# Clock_Led_7_thanh_Huynh_Tan_Cuong.net
KiCad netlist of a schematic drawn in Altium Designer
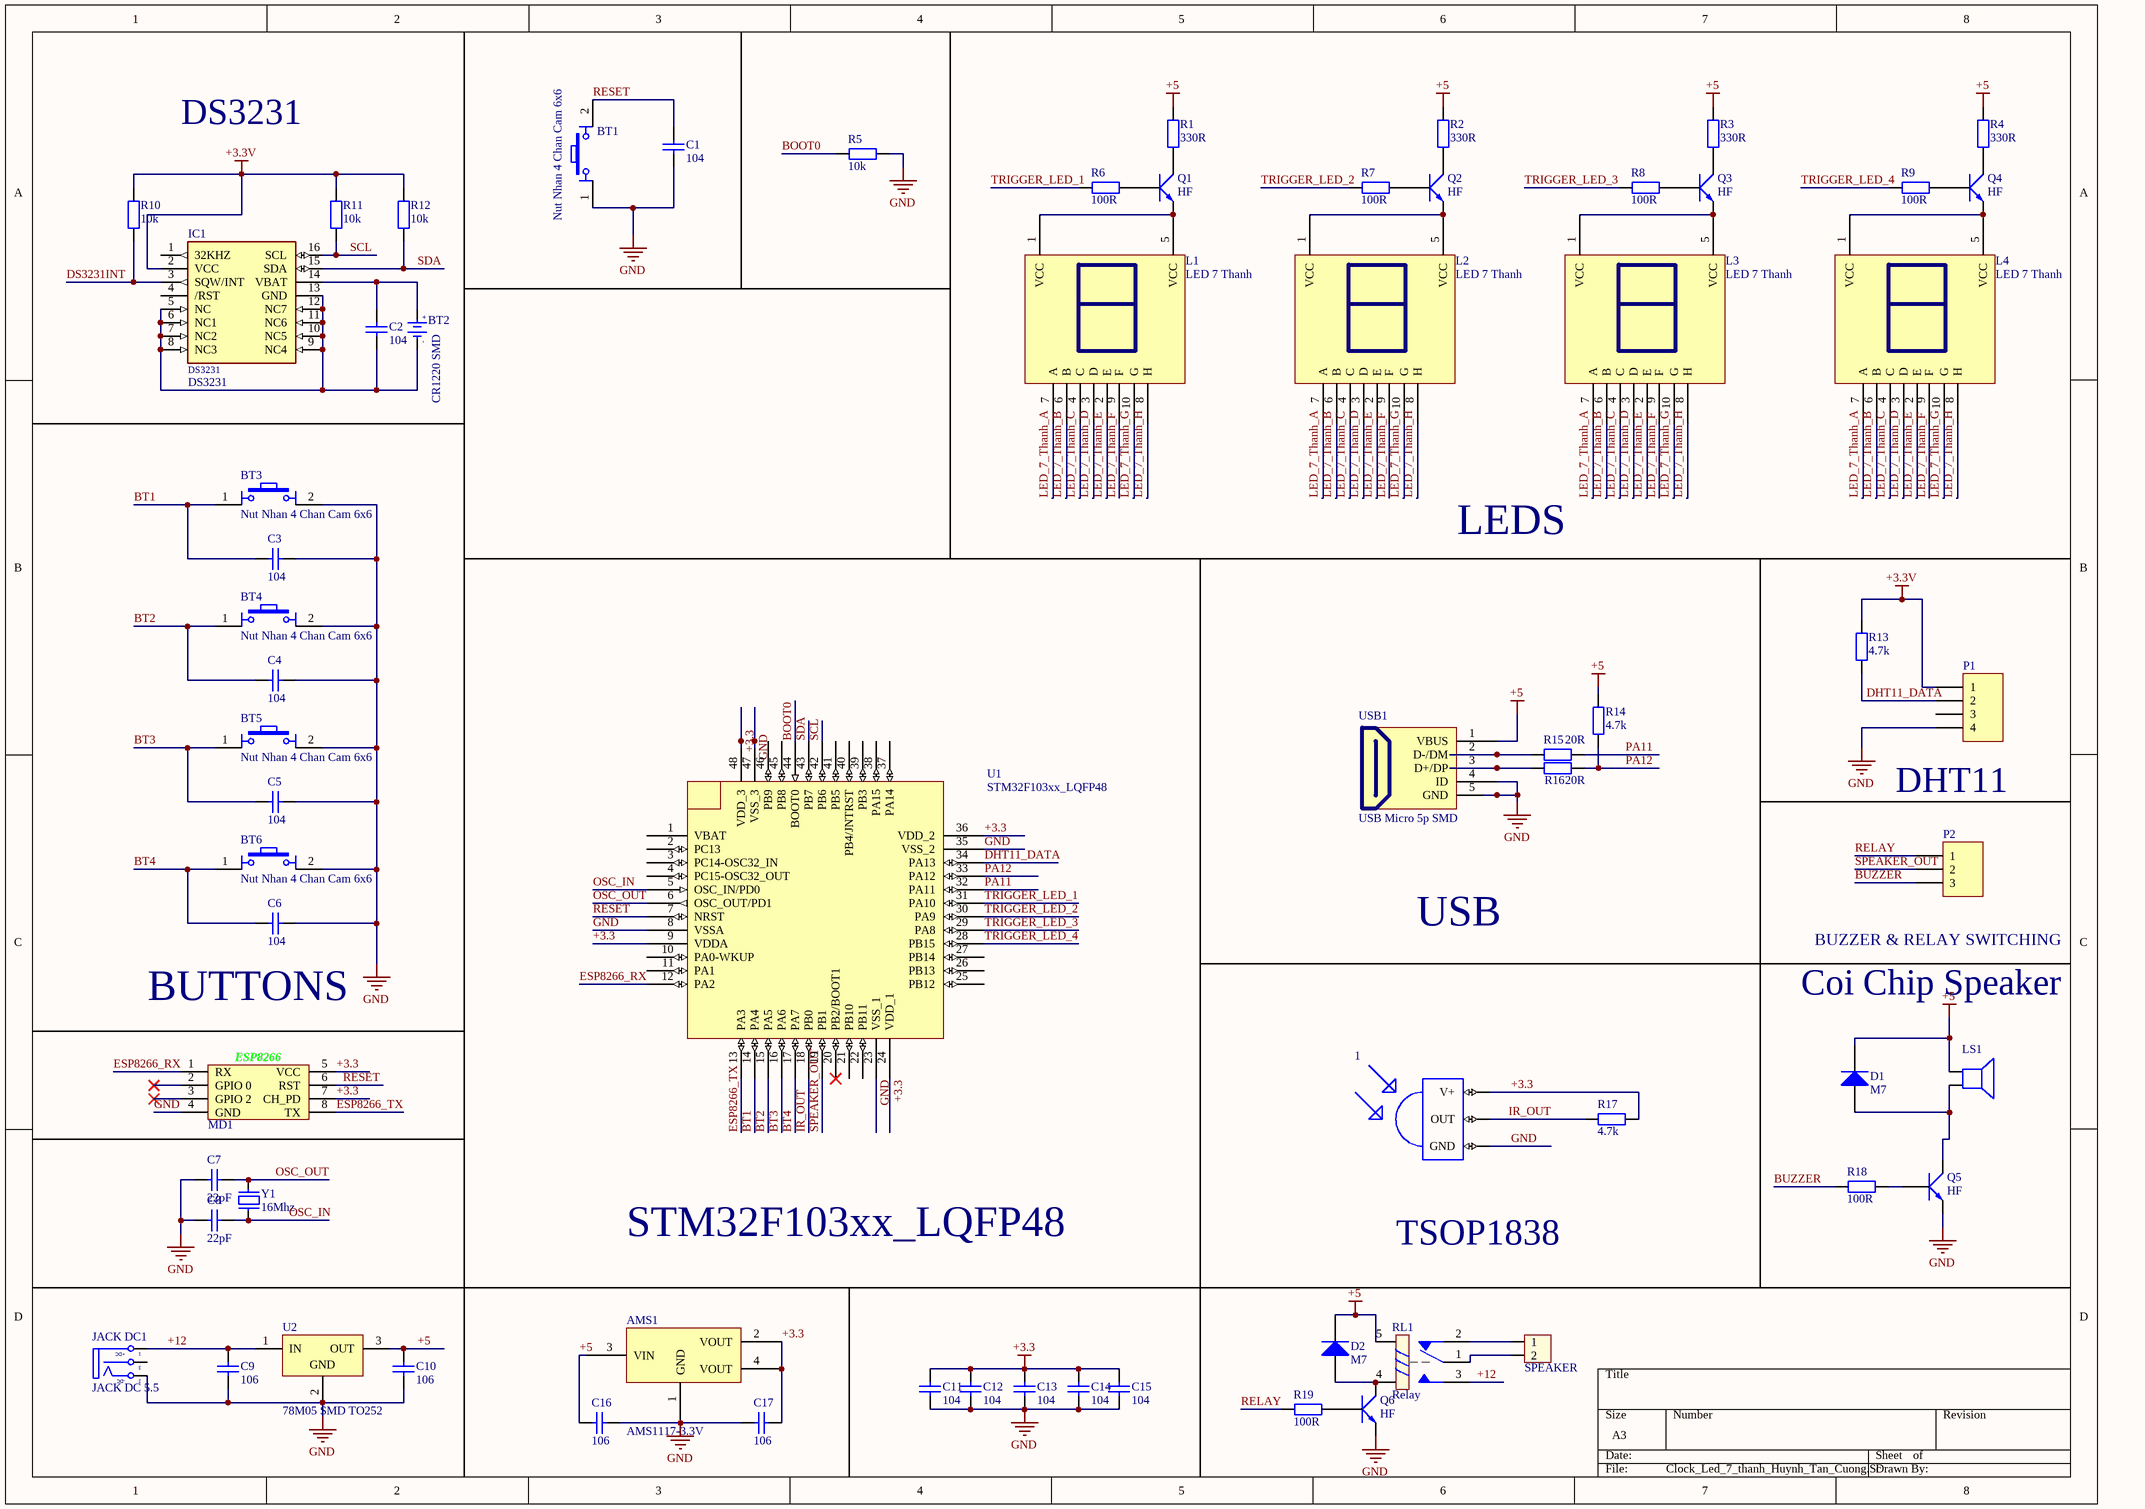
[diagram p0: Clock_Led_7_thanh_Huynh_Tan_Cuong.SchDoc]

(export (version "E")
  (design (tool "Eeschema 10.0.6"))
  (components
    (comp (ref "1")
      (value "TSOP1838")
      (footprint "TSOP18XX")
      (description "IR Remote Receiver 38KHz 35m 3-Pin")
      (fields (field (name "MF") "Vishay"))
      (libsource (lib "TSOP1838") (part "TSOP1838"))
    )
    (comp (ref "AMS1")
      (value "AMS1117-3.3V")
      (footprint "SOT223")
      (description "Dán")
      (libsource (lib "Altium_Lib_by_KhueNguyenCreator") (part "AMS1117 SMD"))
    )
    (comp (ref "BT1")
      (value "Nut Nhan 4 Chan Cam 6x6")
      (footprint "Nut Nhan 4 Chan Cam 6x6")
      (description "Nut Nhan 4 Chan 6x6mm")
      (libsource (lib "") (part "Nut Nhan 4 Chan Cam 6x6_1"))
    )
    (comp (ref "BT2")
      (value "CR1220 SMD")
      (footprint "DE PIN CR1220")
      (libsource (lib "Altium_Lib_by_KhueNguyenCreator") (part "De pin CR1220 SMD"))
    )
    (comp (ref "BT3")
      (value "Nut Nhan 4 Chan Cam 6x6")
      (footprint "Nut Nhan 4 Chan Cam 6x6")
      (description "Nut Nhan 4 Chan 6x6mm")
      (libsource (lib "Altium_Lib_by_KhueNguyenCreator") (part "Nut Nhan 4 Chan Cam 6x6"))
    )
    (comp (ref "BT4")
      (value "Nut Nhan 4 Chan Cam 6x6")
      (footprint "Nut Nhan 4 Chan Cam 6x6")
      (description "Nut Nhan 4 Chan 6x6mm")
      (libsource (lib "Altium_Lib_by_KhueNguyenCreator") (part "Nut Nhan 4 Chan Cam 6x6"))
    )
    (comp (ref "BT5")
      (value "Nut Nhan 4 Chan Cam 6x6")
      (footprint "Nut Nhan 4 Chan Cam 6x6")
      (description "Nut Nhan 4 Chan 6x6mm")
      (libsource (lib "Altium_Lib_by_KhueNguyenCreator") (part "Nut Nhan 4 Chan Cam 6x6"))
    )
    (comp (ref "BT6")
      (value "Nut Nhan 4 Chan Cam 6x6")
      (footprint "Nut Nhan 4 Chan Cam 6x6")
      (description "Nut Nhan 4 Chan 6x6mm")
      (libsource (lib "Altium_Lib_by_KhueNguyenCreator") (part "Nut Nhan 4 Chan Cam 6x6"))
    )
    (comp (ref "C1")
      (value "104")
      (footprint "tu 0603")
      (description "Dán")
      (libsource (lib "Altium_Lib_by_KhueNguyenCreator") (part "Tu 0603 104 50V 10%"))
    )
    (comp (ref "C2")
      (value "104")
      (footprint "tu 0603")
      (description "Dán")
      (libsource (lib "Altium_Lib_by_KhueNguyenCreator") (part "Tu 0603 104 50V 10%"))
    )
    (comp (ref "C3")
      (value "104")
      (footprint "tu 0603")
      (description "Dán")
      (libsource (lib "Altium_Lib_by_KhueNguyenCreator") (part "Tu 0603 104 50V 10%"))
    )
    (comp (ref "C4")
      (value "104")
      (footprint "tu 0603")
      (description "Dán")
      (libsource (lib "Altium_Lib_by_KhueNguyenCreator") (part "Tu 0603 104 50V 10%"))
    )
    (comp (ref "C5")
      (value "104")
      (footprint "tu 0603")
      (description "Dán")
      (libsource (lib "Altium_Lib_by_KhueNguyenCreator") (part "Tu 0603 104 50V 10%"))
    )
    (comp (ref "C6")
      (value "104")
      (footprint "tu 0603")
      (description "Dán")
      (libsource (lib "Altium_Lib_by_KhueNguyenCreator") (part "Tu 0603 104 50V 10%"))
    )
    (comp (ref "C7")
      (value "22pF")
      (footprint "tu 0603")
      (description "Dán")
      (libsource (lib "Altium_Lib_by_KhueNguyenCreator") (part "Tu 0603 22pF 50V 10%"))
    )
    (comp (ref "C8")
      (value "22pF")
      (footprint "tu 0603")
      (description "Dán")
      (libsource (lib "Altium_Lib_by_KhueNguyenCreator") (part "Tu 0603 22pF 50V 10%"))
    )
    (comp (ref "C9")
      (value "106")
      (footprint "tu 0603")
      (description "Dán")
      (libsource (lib "Altium_Lib_by_KhueNguyenCreator") (part "Tu 0603 106 16V 20%"))
    )
    (comp (ref "C10")
      (value "106")
      (footprint "tu 0603")
      (description "Dán")
      (libsource (lib "Altium_Lib_by_KhueNguyenCreator") (part "Tu 0603 106 16V 20%"))
    )
    (comp (ref "C11")
      (value "104")
      (footprint "tu 0603")
      (description "Dán")
      (libsource (lib "Altium_Lib_by_KhueNguyenCreator") (part "Tu 0603 104 50V 10%"))
    )
    (comp (ref "C12")
      (value "104")
      (footprint "tu 0603")
      (description "Dán")
      (libsource (lib "Altium_Lib_by_KhueNguyenCreator") (part "Tu 0603 104 50V 10%"))
    )
    (comp (ref "C13")
      (value "104")
      (footprint "tu 0603")
      (description "Dán")
      (libsource (lib "Altium_Lib_by_KhueNguyenCreator") (part "Tu 0603 104 50V 10%"))
    )
    (comp (ref "C14")
      (value "104")
      (footprint "tu 0603")
      (description "Dán")
      (libsource (lib "Altium_Lib_by_KhueNguyenCreator") (part "Tu 0603 104 50V 10%"))
    )
    (comp (ref "C15")
      (value "104")
      (footprint "tu 0603")
      (description "Dán")
      (libsource (lib "Altium_Lib_by_KhueNguyenCreator") (part "Tu 0603 104 50V 10%"))
    )
    (comp (ref "C16")
      (value "106")
      (footprint "tu 0603")
      (description "Dán")
      (libsource (lib "Altium_Lib_by_KhueNguyenCreator") (part "Tu 0603 106 16V 20%"))
    )
    (comp (ref "C17")
      (value "106")
      (footprint "tu 0603")
      (description "Dán")
      (libsource (lib "Altium_Lib_by_KhueNguyenCreator") (part "Tu 0603 106 16V 20%"))
    )
    (comp (ref "D1")
      (value "M7")
      (footprint "DIODE SMA")
      (description "Dán")
      (libsource (lib "Altium_Lib_by_KhueNguyenCreator") (part "Diode M7 ( 4007 )"))
    )
    (comp (ref "D2")
      (value "M7")
      (footprint "DIODE SMA")
      (description "Dán")
      (libsource (lib "Altium_Lib_by_KhueNguyenCreator") (part "Diode M7 ( 4007 )"))
    )
    (comp (ref "H1")
      (value "SPEAKER")
      (footprint "XH2.54M-2")
      (description "Cắm")
      (libsource (lib "Altium_Lib_by_KhueNguyenCreator") (part "Header 2P 2.54 Duc Thang"))
    )
    (comp (ref "IC1")
      (value "DS3231")
      (footprint "SO16W")
      (description "å®žæ—¶æ—¶é’Ÿï¼ˆRTCï¼‰ICæ—¶é’Ÿ/æ—¥åŽ†IÂ²Cï¼Œ2çº¿ä¸²è¡Œ16-SOICï¼ˆ0.295â€œï¼Œ7.50mmå®½åº¦ï¼‰")
      (fields (field (name "MF") "Maxim Integrated"))
      (libsource (lib "DS3231") (part "DS3231"))
    )
    (comp (ref "JACK DC1")
      (value "JACK DC 5.5")
      (footprint "JACK DC 5.5")
      (libsource (lib "Altium_Lib_by_KhueNguyenCreator") (part "JACK DC 5.5"))
    )
    (comp (ref "L1")
      (value "LED 7 Thanh")
      (footprint "LED7SEG_2.3inch")
      (description "Dán")
      (libsource (lib "Altium_Lib_by_KhueNguyenCreator") (part "LED 7x1 2.3inch Anot"))
    )
    (comp (ref "L2")
      (value "LED 7 Thanh")
      (footprint "LED7SEG_2.3inch")
      (description "Dán")
      (libsource (lib "Altium_Lib_by_KhueNguyenCreator") (part "LED 7x1 2.3inch Anot"))
    )
    (comp (ref "L3")
      (value "LED 7 Thanh")
      (footprint "LED7SEG_2.3inch")
      (description "Dán")
      (libsource (lib "Altium_Lib_by_KhueNguyenCreator") (part "LED 7x1 2.3inch Anot"))
    )
    (comp (ref "L4")
      (value "LED 7 Thanh")
      (footprint "LED7SEG_2.3inch")
      (description "Dán")
      (libsource (lib "Altium_Lib_by_KhueNguyenCreator") (part "LED 7x1 2.3inch Anot"))
    )
    (comp (ref "LS1")
      (value "Coi Chip Speaker")
      (footprint "Coi Chip Speacker")
      (description "Còi chip")
      (libsource (lib "Altium_Lib_by_KhueNguyenCreator") (part "Coi Chip Speaker"))
    )
    (comp (ref "MD1")
      (value "ESP8266 Module")
      (footprint "ESP2866 Module")
      (libsource (lib "Altium_Lib_by_KhueNguyenCreator") (part "ESP8266 Module"))
    )
    (comp (ref "P1")
      (value "DHT11")
      (footprint "HDR1X4H")
      (description "Header, 4-Pin, Right Angle")
      (fields (field (name "PUBLISHER") "Altium Limited"))
      (libsource (lib "Miscellaneous Connectors") (part "Header 4H"))
    )
    (comp (ref "P2")
      (value "BUZZER & RELAY SWITCHING")
      (footprint "HDR1X3")
      (description "Header, 3-Pin")
      (fields (field (name "PUBLISHER") "Altium Limited"))
      (libsource (lib "Miscellaneous Connectors") (part "Header 3"))
    )
    (comp (ref "Q1")
      (value "HF")
      (footprint "SOT23")
      (description "NPN transistor")
      (libsource (lib "Altium_Lib_by_KhueNguyenCreator") (part "C1815 HF SMD"))
    )
    (comp (ref "Q2")
      (value "HF")
      (footprint "SOT23")
      (description "NPN transistor")
      (libsource (lib "Altium_Lib_by_KhueNguyenCreator") (part "C1815 HF SMD"))
    )
    (comp (ref "Q3")
      (value "HF")
      (footprint "SOT23")
      (description "NPN transistor")
      (libsource (lib "Altium_Lib_by_KhueNguyenCreator") (part "C1815 HF SMD"))
    )
    (comp (ref "Q4")
      (value "HF")
      (footprint "SOT23")
      (description "NPN transistor")
      (libsource (lib "Altium_Lib_by_KhueNguyenCreator") (part "C1815 HF SMD"))
    )
    (comp (ref "Q5")
      (value "HF")
      (footprint "SOT23")
      (description "NPN transistor")
      (libsource (lib "Altium_Lib_by_KhueNguyenCreator") (part "C1815 HF SMD"))
    )
    (comp (ref "Q6")
      (value "HF")
      (footprint "SOT23")
      (description "NPN transistor")
      (libsource (lib "Altium_Lib_by_KhueNguyenCreator") (part "C1815 HF SMD"))
    )
    (comp (ref "R1")
      (value "330R")
      (footprint "tro smd 0603")
      (description "Dán")
      (libsource (lib "Altium_Lib_by_KhueNguyenCreator") (part "Tro 0603 5% 330R"))
    )
    (comp (ref "R2")
      (value "330R")
      (footprint "tro smd 0603")
      (description "Dán")
      (libsource (lib "Altium_Lib_by_KhueNguyenCreator") (part "Tro 0603 5% 330R"))
    )
    (comp (ref "R3")
      (value "330R")
      (footprint "tro smd 0603")
      (description "Dán")
      (libsource (lib "Altium_Lib_by_KhueNguyenCreator") (part "Tro 0603 5% 330R"))
    )
    (comp (ref "R4")
      (value "330R")
      (footprint "tro smd 0603")
      (description "Dán")
      (libsource (lib "Altium_Lib_by_KhueNguyenCreator") (part "Tro 0603 5% 330R"))
    )
    (comp (ref "R5")
      (value "10k")
      (footprint "tro smd 0603")
      (description "Dán")
      (libsource (lib "Altium_Lib_by_KhueNguyenCreator") (part "Tro 0603 1% 10k"))
    )
    (comp (ref "R6")
      (value "100R")
      (footprint "tro smd 1206")
      (description "Dán")
      (libsource (lib "Altium_Lib_by_KhueNguyenCreator") (part "Tro 1206 1% 100R"))
    )
    (comp (ref "R7")
      (value "100R")
      (footprint "tro smd 1206")
      (description "Dán")
      (libsource (lib "Altium_Lib_by_KhueNguyenCreator") (part "Tro 1206 1% 100R"))
    )
    (comp (ref "R8")
      (value "100R")
      (footprint "tro smd 1206")
      (description "Dán")
      (libsource (lib "Altium_Lib_by_KhueNguyenCreator") (part "Tro 1206 1% 100R"))
    )
    (comp (ref "R9")
      (value "100R")
      (footprint "tro smd 1206")
      (description "Dán")
      (libsource (lib "Altium_Lib_by_KhueNguyenCreator") (part "Tro 1206 1% 100R"))
    )
    (comp (ref "R10")
      (value "10k")
      (footprint "tro smd 0603")
      (description "Dán")
      (libsource (lib "Altium_Lib_by_KhueNguyenCreator") (part "Tro 0603 1% 10k"))
    )
    (comp (ref "R11")
      (value "10k")
      (footprint "tro smd 0603")
      (description "Dán")
      (libsource (lib "Altium_Lib_by_KhueNguyenCreator") (part "Tro 0603 1% 10k"))
    )
    (comp (ref "R12")
      (value "10k")
      (footprint "tro smd 0603")
      (description "Dán")
      (libsource (lib "Altium_Lib_by_KhueNguyenCreator") (part "Tro 0603 1% 10k"))
    )
    (comp (ref "R13")
      (value "4.7k")
      (footprint "tro smd 0603")
      (description "Dán")
      (libsource (lib "Altium_Lib_by_KhueNguyenCreator") (part "Tro 0603 5% 4.7k"))
    )
    (comp (ref "R14")
      (value "4.7k")
      (footprint "tro smd 0603")
      (description "Dán")
      (libsource (lib "Altium_Lib_by_KhueNguyenCreator") (part "Tro 0603 5% 4.7k"))
    )
    (comp (ref "R15")
      (value "20R")
      (footprint "tro smd 1206")
      (description "Dán")
      (libsource (lib "Altium_Lib_by_KhueNguyenCreator") (part "Tro 1206 5% 20R"))
    )
    (comp (ref "R16")
      (value "20R")
      (footprint "tro smd 1206")
      (description "Dán")
      (libsource (lib "Altium_Lib_by_KhueNguyenCreator") (part "Tro 1206 5% 20R"))
    )
    (comp (ref "R17")
      (value "4.7k")
      (footprint "tro smd 0603")
      (description "Dán")
      (libsource (lib "Altium_Lib_by_KhueNguyenCreator") (part "Tro 0603 5% 4.7k"))
    )
    (comp (ref "R18")
      (value "100R")
      (footprint "tro smd 0603")
      (description "Dán")
      (libsource (lib "Altium_Lib_by_KhueNguyenCreator") (part "Tro 0603 5% 100R"))
    )
    (comp (ref "R19")
      (value "100R")
      (footprint "tro smd 0603")
      (description "Dán")
      (libsource (lib "Altium_Lib_by_KhueNguyenCreator") (part "Tro 0603 5% 100R"))
    )
    (comp (ref "RL1")
      (value "Relay")
      (footprint "Relay 5 Chan SRD")
      (description "Relay 5 Chan")
      (libsource (lib "Altium_Lib_by_KhueNguyenCreator") (part "Relay 5 Chan SRD"))
    )
    (comp (ref "U1")
      (value "STM32F103xx_LQFP48")
      (footprint "STM32_LQPF48")
      (fields (field (name "PUBLISHER") "Altium Limited"))
      (libsource (lib "Altium_Lib_by_KhueNguyenCreator") (part "STM32F103xx_LQFP48"))
    )
    (comp (ref "U2")
      (value "78M05 SMD TO252")
      (footprint "TO252")
      (description "Dán")
      (libsource (lib "Altium_Lib_by_KhueNguyenCreator") (part "78M05 SMD TO252"))
    )
    (comp (ref "USB1")
      (value "USB Micro 5p SMD")
      (footprint "USB Micro 5p SMD")
      (description "USB Type B")
      (libsource (lib "Altium_Lib_by_KhueNguyenCreator") (part "USB Micro 5p SMD"))
    )
    (comp (ref "Y1")
      (value "16Mhz")
      (footprint "Thach Anh 2 chan SMD")
      (description "Crystal For all Crystal 2pin.")
      (libsource (lib "Altium_Lib_by_KhueNguyenCreator") (part "Thach Anh 2 chan SMD"))
    )
  )
  (nets
    (net (code "1") (name "+3.3") (class "Default")
      (node (ref "1") (pin "VCC") (pinfunction "V+_VCC") (pintype "bidirectional"))
      (node (ref "AMS1") (pin "2") (pinfunction "VOUT_2") (pintype "passive"))
      (node (ref "AMS1") (pin "4") (pinfunction "VOUT_4") (pintype "passive"))
      (node (ref "C11") (pin "1") (pinfunction "1_1") (pintype "passive"))
      (node (ref "C12") (pin "1") (pinfunction "1_1") (pintype "passive"))
      (node (ref "C13") (pin "1") (pinfunction "1_1") (pintype "passive"))
      (node (ref "C14") (pin "1") (pinfunction "1_1") (pintype "passive"))
      (node (ref "C15") (pin "1") (pinfunction "1_1") (pintype "passive"))
      (node (ref "C17") (pin "2") (pinfunction "2_2") (pintype "passive"))
      (node (ref "MD1") (pin "5") (pinfunction "VCC_5") (pintype "passive"))
      (node (ref "MD1") (pin "7") (pinfunction "CH_PD_7") (pintype "passive"))
      (node (ref "R17") (pin "2") (pinfunction "2_2") (pintype "passive"))
      (node (ref "U1") (pin "24") (pinfunction "VDD_1_24") (pintype "power_in"))
      (node (ref "U1") (pin "36") (pinfunction "VDD_2_36") (pintype "power_in"))
      (node (ref "U1") (pin "48") (pinfunction "VDD_3_48") (pintype "power_in"))
      (node (ref "U1") (pin "9") (pinfunction "VDDA_9") (pintype "power_in"))
    )
    (net (code "2") (name "+3.3V") (class "Default")
      (node (ref "IC1") (pin "2") (pinfunction "VCC_2") (pintype "power_in"))
      (node (ref "P1") (pin "1") (pinfunction "1_1") (pintype "passive"))
      (node (ref "R10") (pin "2") (pinfunction "2_2") (pintype "passive"))
      (node (ref "R11") (pin "2") (pinfunction "2_2") (pintype "passive"))
      (node (ref "R12") (pin "2") (pinfunction "2_2") (pintype "passive"))
      (node (ref "R13") (pin "2") (pinfunction "2_2") (pintype "passive"))
    )
    (net (code "3") (name "+5") (class "Default")
      (node (ref "AMS1") (pin "3") (pinfunction "VIN_3") (pintype "passive"))
      (node (ref "C10") (pin "1") (pinfunction "1_1") (pintype "passive"))
      (node (ref "C16") (pin "1") (pinfunction "1_1") (pintype "passive"))
      (node (ref "D1") (pin "2") (pinfunction "K_2") (pintype "passive"))
      (node (ref "D2") (pin "2") (pinfunction "K_2") (pintype "passive"))
      (node (ref "LS1") (pin "1") (pinfunction "1_1") (pintype "passive"))
      (node (ref "R1") (pin "2") (pinfunction "2_2") (pintype "passive"))
      (node (ref "R14") (pin "2") (pinfunction "2_2") (pintype "passive"))
      (node (ref "R2") (pin "2") (pinfunction "2_2") (pintype "passive"))
      (node (ref "R3") (pin "2") (pinfunction "2_2") (pintype "passive"))
      (node (ref "R4") (pin "2") (pinfunction "2_2") (pintype "passive"))
      (node (ref "RL1") (pin "5") (pinfunction "5_5") (pintype "passive"))
      (node (ref "U2") (pin "3") (pinfunction "OUT_3") (pintype "power_in"))
      (node (ref "USB1") (pin "1") (pinfunction "VBUS_1") (pintype "passive"))
    )
    (net (code "4") (name "/+12") (class "Default")
      (node (ref "C9") (pin "1") (pinfunction "1_1") (pintype "passive"))
      (node (ref "JACK DC1") (pin "1") (pinfunction "T_1") (pintype "passive"))
      (node (ref "RL1") (pin "3") (pinfunction "3_3") (pintype "passive"))
      (node (ref "U2") (pin "1") (pinfunction "IN_1") (pintype "power_in"))
    )
    (net (code "5") (name "/BOOT0") (class "Default")
      (node (ref "R5") (pin "1") (pinfunction "1_1") (pintype "passive"))
      (node (ref "U1") (pin "44") (pinfunction "BOOT0_44") (pintype "input"))
    )
    (net (code "6") (name "/BT1") (class "Default")
      (node (ref "BT3") (pin "1") (pintype "passive"))
      (node (ref "C3") (pin "1") (pinfunction "1_1") (pintype "passive"))
      (node (ref "U1") (pin "14") (pinfunction "PA4_14") (pintype "bidirectional"))
    )
    (net (code "7") (name "/BT2") (class "Default")
      (node (ref "BT4") (pin "1") (pintype "passive"))
      (node (ref "C4") (pin "1") (pinfunction "1_1") (pintype "passive"))
      (node (ref "U1") (pin "15") (pinfunction "PA5_15") (pintype "bidirectional"))
    )
    (net (code "8") (name "/BT3") (class "Default")
      (node (ref "BT5") (pin "1") (pintype "passive"))
      (node (ref "C5") (pin "1") (pinfunction "1_1") (pintype "passive"))
      (node (ref "U1") (pin "16") (pinfunction "PA6_16") (pintype "bidirectional"))
    )
    (net (code "9") (name "/BT4") (class "Default")
      (node (ref "BT6") (pin "1") (pintype "passive"))
      (node (ref "C6") (pin "1") (pinfunction "1_1") (pintype "passive"))
      (node (ref "U1") (pin "17") (pinfunction "PA7_17") (pintype "bidirectional"))
    )
    (net (code "10") (name "/BUZZER") (class "Default")
      (node (ref "P2") (pin "3") (pinfunction "3_3") (pintype "passive"))
      (node (ref "R18") (pin "1") (pinfunction "1_1") (pintype "passive"))
    )
    (net (code "11") (name "/DHT11_DATA") (class "Default")
      (node (ref "P1") (pin "2") (pinfunction "2_2") (pintype "passive"))
      (node (ref "R13") (pin "1") (pinfunction "1_1") (pintype "passive"))
      (node (ref "U1") (pin "34") (pinfunction "PA13_34") (pintype "bidirectional"))
    )
    (net (code "12") (name "/DS3231INT") (class "Default")
      (node (ref "IC1") (pin "3") (pinfunction "SQW/INT_3") (pintype "output"))
      (node (ref "R10") (pin "1") (pinfunction "1_1") (pintype "passive"))
    )
    (net (code "13") (name "/ESP8266_RX") (class "Default")
      (node (ref "MD1") (pin "1") (pinfunction "RX_1") (pintype "passive"))
      (node (ref "U1") (pin "12") (pinfunction "PA2_12") (pintype "bidirectional"))
    )
    (net (code "14") (name "/ESP8266_TX") (class "Default")
      (node (ref "MD1") (pin "8") (pinfunction "TX_8") (pintype "passive"))
      (node (ref "U1") (pin "13") (pinfunction "PA3_13") (pintype "bidirectional"))
    )
    (net (code "15") (name "/IR_OUT") (class "Default")
      (node (ref "1") (pin "OUT") (pinfunction "OUT_OUT") (pintype "bidirectional"))
      (node (ref "R17") (pin "1") (pinfunction "1_1") (pintype "passive"))
      (node (ref "U1") (pin "18") (pinfunction "PB0_18") (pintype "bidirectional"))
    )
    (net (code "16") (name "/LED_7_Thanh_A") (class "Default")
      (node (ref "L1") (pin "7") (pinfunction "A_7") (pintype "passive"))
      (node (ref "L2") (pin "7") (pinfunction "A_7") (pintype "passive"))
      (node (ref "L3") (pin "7") (pinfunction "A_7") (pintype "passive"))
      (node (ref "L4") (pin "7") (pinfunction "A_7") (pintype "passive"))
    )
    (net (code "17") (name "/LED_7_Thanh_B") (class "Default")
      (node (ref "L1") (pin "6") (pinfunction "B_6") (pintype "passive"))
      (node (ref "L2") (pin "6") (pinfunction "B_6") (pintype "passive"))
      (node (ref "L3") (pin "6") (pinfunction "B_6") (pintype "passive"))
      (node (ref "L4") (pin "6") (pinfunction "B_6") (pintype "passive"))
    )
    (net (code "18") (name "/LED_7_Thanh_C") (class "Default")
      (node (ref "L1") (pin "4") (pinfunction "C_4") (pintype "passive"))
      (node (ref "L2") (pin "4") (pinfunction "C_4") (pintype "passive"))
      (node (ref "L3") (pin "4") (pinfunction "C_4") (pintype "passive"))
      (node (ref "L4") (pin "4") (pinfunction "C_4") (pintype "passive"))
    )
    (net (code "19") (name "/LED_7_Thanh_D") (class "Default")
      (node (ref "L1") (pin "3") (pinfunction "D_3") (pintype "passive"))
      (node (ref "L2") (pin "3") (pinfunction "D_3") (pintype "passive"))
      (node (ref "L3") (pin "3") (pinfunction "D_3") (pintype "passive"))
      (node (ref "L4") (pin "3") (pinfunction "D_3") (pintype "passive"))
    )
    (net (code "20") (name "/LED_7_Thanh_E") (class "Default")
      (node (ref "L1") (pin "2") (pinfunction "E_2") (pintype "passive"))
      (node (ref "L2") (pin "2") (pinfunction "E_2") (pintype "passive"))
      (node (ref "L3") (pin "2") (pinfunction "E_2") (pintype "passive"))
      (node (ref "L4") (pin "2") (pinfunction "E_2") (pintype "passive"))
    )
    (net (code "21") (name "/LED_7_Thanh_F") (class "Default")
      (node (ref "L1") (pin "9") (pinfunction "F_9") (pintype "passive"))
      (node (ref "L2") (pin "9") (pinfunction "F_9") (pintype "passive"))
      (node (ref "L3") (pin "9") (pinfunction "F_9") (pintype "passive"))
      (node (ref "L4") (pin "9") (pinfunction "F_9") (pintype "passive"))
    )
    (net (code "22") (name "/LED_7_Thanh_G") (class "Default")
      (node (ref "L1") (pin "10") (pinfunction "G_10") (pintype "passive"))
      (node (ref "L2") (pin "10") (pinfunction "G_10") (pintype "passive"))
      (node (ref "L3") (pin "10") (pinfunction "G_10") (pintype "passive"))
      (node (ref "L4") (pin "10") (pinfunction "G_10") (pintype "passive"))
    )
    (net (code "23") (name "/LED_7_Thanh_H") (class "Default")
      (node (ref "L1") (pin "8") (pinfunction "H_8") (pintype "passive"))
      (node (ref "L2") (pin "8") (pinfunction "H_8") (pintype "passive"))
      (node (ref "L3") (pin "8") (pinfunction "H_8") (pintype "passive"))
      (node (ref "L4") (pin "8") (pinfunction "H_8") (pintype "passive"))
    )
    (net (code "24") (name "/OSC_IN") (class "Default")
      (node (ref "C8") (pin "1") (pinfunction "1_1") (pintype "passive"))
      (node (ref "U1") (pin "5") (pinfunction "OSC_IN/PD0_5") (pintype "input"))
      (node (ref "Y1") (pin "1") (pinfunction "1_1") (pintype "passive"))
    )
    (net (code "25") (name "/OSC_OUT") (class "Default")
      (node (ref "C7") (pin "1") (pinfunction "1_1") (pintype "passive"))
      (node (ref "U1") (pin "6") (pinfunction "OSC_OUT/PD1_6") (pintype "output"))
      (node (ref "Y1") (pin "2") (pinfunction "2_2") (pintype "passive"))
    )
    (net (code "26") (name "/PA11") (class "Default")
      (node (ref "R15") (pin "2") (pinfunction "2_2") (pintype "passive"))
      (node (ref "U1") (pin "32") (pinfunction "PA11_32") (pintype "bidirectional"))
    )
    (net (code "27") (name "/PA12") (class "Default")
      (node (ref "R14") (pin "1") (pinfunction "1_1") (pintype "passive"))
      (node (ref "R16") (pin "2") (pinfunction "2_2") (pintype "passive"))
      (node (ref "U1") (pin "33") (pinfunction "PA12_33") (pintype "bidirectional"))
    )
    (net (code "28") (name "/RELAY") (class "Default")
      (node (ref "P2") (pin "1") (pinfunction "1_1") (pintype "passive"))
      (node (ref "R19") (pin "1") (pinfunction "1_1") (pintype "passive"))
    )
    (net (code "29") (name "/RESET") (class "Default")
      (node (ref "BT1") (pin "2") (pintype "passive"))
      (node (ref "C1") (pin "1") (pinfunction "1_1") (pintype "passive"))
      (node (ref "MD1") (pin "6") (pinfunction "RST_6") (pintype "passive"))
      (node (ref "U1") (pin "7") (pinfunction "NRST_7") (pintype "bidirectional"))
    )
    (net (code "30") (name "/SCL") (class "Default")
      (node (ref "IC1") (pin "16") (pinfunction "SCL_16") (pintype "bidirectional"))
      (node (ref "R11") (pin "1") (pinfunction "1_1") (pintype "passive"))
      (node (ref "U1") (pin "42") (pinfunction "PB6_42") (pintype "bidirectional"))
    )
    (net (code "31") (name "/SDA") (class "Default")
      (node (ref "IC1") (pin "15") (pinfunction "SDA_15") (pintype "bidirectional"))
      (node (ref "R12") (pin "1") (pinfunction "1_1") (pintype "passive"))
      (node (ref "U1") (pin "43") (pinfunction "PB7_43") (pintype "bidirectional"))
    )
    (net (code "32") (name "/SPEAKER_OUT") (class "Default")
      (node (ref "P2") (pin "2") (pinfunction "2_2") (pintype "passive"))
      (node (ref "U1") (pin "19") (pinfunction "PB1_19") (pintype "bidirectional"))
    )
    (net (code "33") (name "/TRIGGER_LED_1") (class "Default")
      (node (ref "R6") (pin "1") (pinfunction "1_1") (pintype "passive"))
      (node (ref "U1") (pin "31") (pinfunction "PA10_31") (pintype "bidirectional"))
    )
    (net (code "34") (name "/TRIGGER_LED_2") (class "Default")
      (node (ref "R7") (pin "1") (pinfunction "1_1") (pintype "passive"))
      (node (ref "U1") (pin "30") (pinfunction "PA9_30") (pintype "bidirectional"))
    )
    (net (code "35") (name "/TRIGGER_LED_3") (class "Default")
      (node (ref "R8") (pin "1") (pinfunction "1_1") (pintype "passive"))
      (node (ref "U1") (pin "29") (pinfunction "PA8_29") (pintype "bidirectional"))
    )
    (net (code "36") (name "/TRIGGER_LED_4") (class "Default")
      (node (ref "R9") (pin "1") (pinfunction "1_1") (pintype "passive"))
      (node (ref "U1") (pin "28") (pinfunction "PB15_28") (pintype "bidirectional"))
    )
    (net (code "37") (name "GND") (class "Default")
      (node (ref "1") (pin "GND") (pinfunction "GND_GND") (pintype "bidirectional"))
      (node (ref "AMS1") (pin "1") (pinfunction "GND_1") (pintype "passive"))
      (node (ref "BT1") (pin "1") (pintype "passive"))
      (node (ref "BT3") (pin "2") (pintype "passive"))
      (node (ref "BT4") (pin "2") (pintype "passive"))
      (node (ref "BT5") (pin "2") (pintype "passive"))
      (node (ref "BT6") (pin "2") (pintype "passive"))
      (node (ref "C1") (pin "2") (pinfunction "2_2") (pintype "passive"))
      (node (ref "C10") (pin "2") (pinfunction "2_2") (pintype "passive"))
      (node (ref "C11") (pin "2") (pinfunction "2_2") (pintype "passive"))
      (node (ref "C12") (pin "2") (pinfunction "2_2") (pintype "passive"))
      (node (ref "C13") (pin "2") (pinfunction "2_2") (pintype "passive"))
      (node (ref "C14") (pin "2") (pinfunction "2_2") (pintype "passive"))
      (node (ref "C15") (pin "2") (pinfunction "2_2") (pintype "passive"))
      (node (ref "C16") (pin "2") (pinfunction "2_2") (pintype "passive"))
      (node (ref "C17") (pin "1") (pinfunction "1_1") (pintype "passive"))
      (node (ref "C3") (pin "2") (pinfunction "2_2") (pintype "passive"))
      (node (ref "C4") (pin "2") (pinfunction "2_2") (pintype "passive"))
      (node (ref "C5") (pin "2") (pinfunction "2_2") (pintype "passive"))
      (node (ref "C6") (pin "2") (pinfunction "2_2") (pintype "passive"))
      (node (ref "C7") (pin "2") (pinfunction "2_2") (pintype "passive"))
      (node (ref "C8") (pin "2") (pinfunction "2_2") (pintype "passive"))
      (node (ref "C9") (pin "2") (pinfunction "2_2") (pintype "passive"))
      (node (ref "JACK DC1") (pin "2") (pinfunction "TN_2") (pintype "passive"))
      (node (ref "MD1") (pin "4") (pinfunction "GND_4") (pintype "passive"))
      (node (ref "P1") (pin "4") (pinfunction "4_4") (pintype "passive"))
      (node (ref "Q5") (pin "2") (pinfunction "E_2") (pintype "passive"))
      (node (ref "Q6") (pin "2") (pinfunction "E_2") (pintype "passive"))
      (node (ref "R5") (pin "2") (pinfunction "2_2") (pintype "passive"))
      (node (ref "U1") (pin "23") (pinfunction "VSS_1_23") (pintype "power_in"))
      (node (ref "U1") (pin "35") (pinfunction "VSS_2_35") (pintype "power_in"))
      (node (ref "U1") (pin "47") (pinfunction "VSS_3_47") (pintype "power_in"))
      (node (ref "U1") (pin "8") (pinfunction "VSSA_8") (pintype "power_in"))
      (node (ref "U2") (pin "2") (pinfunction "GND_2") (pintype "power_in"))
      (node (ref "USB1") (pin "4") (pinfunction "ID_4") (pintype "passive"))
      (node (ref "USB1") (pin "5") (pinfunction "GND_5") (pintype "passive"))
    )
    (net (code "38") (name "Net-(BT2-+3V)") (class "Default")
      (node (ref "BT2") (pin "1") (pinfunction "+3V_1") (pintype "passive"))
      (node (ref "C2") (pin "1") (pinfunction "1_1") (pintype "passive"))
      (node (ref "IC1") (pin "14") (pinfunction "VBAT_14") (pintype "power_in"))
    )
    (net (code "39") (name "Net-(BT2-GND)") (class "Default")
      (node (ref "BT2") (pin "2") (pinfunction "GND_2") (pintype "passive"))
      (node (ref "C2") (pin "2") (pinfunction "2_2") (pintype "passive"))
      (node (ref "IC1") (pin "10") (pinfunction "NC5_10") (pintype "input"))
      (node (ref "IC1") (pin "11") (pinfunction "NC6_11") (pintype "input"))
      (node (ref "IC1") (pin "12") (pinfunction "NC7_12") (pintype "input"))
      (node (ref "IC1") (pin "13") (pinfunction "GND_13") (pintype "power_in"))
      (node (ref "IC1") (pin "5") (pinfunction "NC_5") (pintype "input"))
      (node (ref "IC1") (pin "6") (pinfunction "NC1_6") (pintype "input"))
      (node (ref "IC1") (pin "7") (pinfunction "NC2_7") (pintype "input"))
      (node (ref "IC1") (pin "8") (pinfunction "NC3_8") (pintype "input"))
      (node (ref "IC1") (pin "9") (pinfunction "NC4_9") (pintype "input"))
    )
    (net (code "40") (name "Net-(D1-A)") (class "Default")
      (node (ref "D1") (pin "1") (pinfunction "A_1") (pintype "passive"))
      (node (ref "LS1") (pin "2") (pinfunction "2_2") (pintype "passive"))
      (node (ref "Q5") (pin "3") (pinfunction "C_3") (pintype "passive"))
    )
    (net (code "41") (name "Net-(D2-A)") (class "Default")
      (node (ref "D2") (pin "1") (pinfunction "A_1") (pintype "passive"))
      (node (ref "Q6") (pin "3") (pinfunction "C_3") (pintype "passive"))
      (node (ref "RL1") (pin "4") (pinfunction "4_4") (pintype "passive"))
    )
    (net (code "42") (name "Net-(H1-Pad1)") (class "Default")
      (node (ref "H1") (pin "1") (pinfunction "1_1") (pintype "passive"))
      (node (ref "RL1") (pin "2") (pinfunction "2_2") (pintype "passive"))
    )
    (net (code "43") (name "Net-(H1-Pad2)") (class "Default")
      (node (ref "H1") (pin "2") (pinfunction "2_2") (pintype "passive"))
      (node (ref "RL1") (pin "1") (pinfunction "1_1") (pintype "passive"))
    )
    (net (code "44") (name "Net-(Q1-B)") (class "Default")
      (node (ref "Q1") (pin "1") (pinfunction "B_1") (pintype "passive"))
      (node (ref "R6") (pin "2") (pinfunction "2_2") (pintype "passive"))
    )
    (net (code "45") (name "Net-(Q1-C)") (class "Default")
      (node (ref "Q1") (pin "3") (pinfunction "C_3") (pintype "passive"))
      (node (ref "R1") (pin "1") (pinfunction "1_1") (pintype "passive"))
    )
    (net (code "46") (name "Net-(Q1-E)") (class "Default")
      (node (ref "L1") (pin "1") (pinfunction "VCC_1") (pintype "passive"))
      (node (ref "L1") (pin "5") (pinfunction "VCC_5") (pintype "passive"))
      (node (ref "Q1") (pin "2") (pinfunction "E_2") (pintype "passive"))
    )
    (net (code "47") (name "Net-(Q2-B)") (class "Default")
      (node (ref "Q2") (pin "1") (pinfunction "B_1") (pintype "passive"))
      (node (ref "R7") (pin "2") (pinfunction "2_2") (pintype "passive"))
    )
    (net (code "48") (name "Net-(Q2-C)") (class "Default")
      (node (ref "Q2") (pin "3") (pinfunction "C_3") (pintype "passive"))
      (node (ref "R2") (pin "1") (pinfunction "1_1") (pintype "passive"))
    )
    (net (code "49") (name "Net-(Q2-E)") (class "Default")
      (node (ref "L2") (pin "1") (pinfunction "VCC_1") (pintype "passive"))
      (node (ref "L2") (pin "5") (pinfunction "VCC_5") (pintype "passive"))
      (node (ref "Q2") (pin "2") (pinfunction "E_2") (pintype "passive"))
    )
    (net (code "50") (name "Net-(Q3-B)") (class "Default")
      (node (ref "Q3") (pin "1") (pinfunction "B_1") (pintype "passive"))
      (node (ref "R8") (pin "2") (pinfunction "2_2") (pintype "passive"))
    )
    (net (code "51") (name "Net-(Q3-C)") (class "Default")
      (node (ref "Q3") (pin "3") (pinfunction "C_3") (pintype "passive"))
      (node (ref "R3") (pin "1") (pinfunction "1_1") (pintype "passive"))
    )
    (net (code "52") (name "Net-(Q3-E)") (class "Default")
      (node (ref "L3") (pin "1") (pinfunction "VCC_1") (pintype "passive"))
      (node (ref "L3") (pin "5") (pinfunction "VCC_5") (pintype "passive"))
      (node (ref "Q3") (pin "2") (pinfunction "E_2") (pintype "passive"))
    )
    (net (code "53") (name "Net-(Q4-B)") (class "Default")
      (node (ref "Q4") (pin "1") (pinfunction "B_1") (pintype "passive"))
      (node (ref "R9") (pin "2") (pinfunction "2_2") (pintype "passive"))
    )
    (net (code "54") (name "Net-(Q4-C)") (class "Default")
      (node (ref "Q4") (pin "3") (pinfunction "C_3") (pintype "passive"))
      (node (ref "R4") (pin "1") (pinfunction "1_1") (pintype "passive"))
    )
    (net (code "55") (name "Net-(Q4-E)") (class "Default")
      (node (ref "L4") (pin "1") (pinfunction "VCC_1") (pintype "passive"))
      (node (ref "L4") (pin "5") (pinfunction "VCC_5") (pintype "passive"))
      (node (ref "Q4") (pin "2") (pinfunction "E_2") (pintype "passive"))
    )
    (net (code "56") (name "Net-(Q5-B)") (class "Default")
      (node (ref "Q5") (pin "1") (pinfunction "B_1") (pintype "passive"))
      (node (ref "R18") (pin "2") (pinfunction "2_2") (pintype "passive"))
    )
    (net (code "57") (name "Net-(Q6-B)") (class "Default")
      (node (ref "Q6") (pin "1") (pinfunction "B_1") (pintype "passive"))
      (node (ref "R19") (pin "2") (pinfunction "2_2") (pintype "passive"))
    )
    (net (code "58") (name "Net-(USB1-D+{slash}DP)") (class "Default")
      (node (ref "R16") (pin "1") (pinfunction "1_1") (pintype "passive"))
      (node (ref "USB1") (pin "3") (pinfunction "D+/DP_3") (pintype "passive"))
    )
    (net (code "59") (name "Net-(USB1-D-{slash}DM)") (class "Default")
      (node (ref "R15") (pin "1") (pinfunction "1_1") (pintype "passive"))
      (node (ref "USB1") (pin "2") (pinfunction "D-/DM_2") (pintype "passive"))
    )
    (net (code "60") (name "unconnected-(IC1-32KHZ-Pad1)") (class "Default")
      (node (ref "IC1") (pin "1") (pinfunction "32KHZ_1") (pintype "output"))
    )
    (net (code "61") (name "unconnected-(IC1-{slash}RST-Pad4)") (class "Default")
      (node (ref "IC1") (pin "4") (pinfunction "/RST_4") (pintype "passive"))
    )
    (net (code "62") (name "unconnected-(JACK DC1-S-Pad3)") (class "Default")
      (node (ref "JACK DC1") (pin "3") (pinfunction "S_3") (pintype "power_in"))
    )
    (net (code "63") (name "unconnected-(MD1-GPIO_0-Pad2)") (class "Default")
      (node (ref "MD1") (pin "2") (pinfunction "GPIO_0_2") (pintype "passive+no_connect"))
    )
    (net (code "64") (name "unconnected-(MD1-GPIO_2-Pad3)") (class "Default")
      (node (ref "MD1") (pin "3") (pinfunction "GPIO_2_3") (pintype "passive+no_connect"))
    )
    (net (code "65") (name "unconnected-(P1-Pad3)") (class "Default")
      (node (ref "P1") (pin "3") (pinfunction "3_3") (pintype "passive"))
    )
    (net (code "66") (name "unconnected-(U1-PA0-WKUP-Pad10)") (class "Default")
      (node (ref "U1") (pin "10") (pinfunction "PA0-WKUP_10") (pintype "bidirectional"))
    )
    (net (code "67") (name "unconnected-(U1-PA1-Pad11)") (class "Default")
      (node (ref "U1") (pin "11") (pinfunction "PA1_11") (pintype "bidirectional"))
    )
    (net (code "68") (name "unconnected-(U1-PA14-Pad37)") (class "Default")
      (node (ref "U1") (pin "37") (pinfunction "PA14_37") (pintype "bidirectional"))
    )
    (net (code "69") (name "unconnected-(U1-PA15-Pad38)") (class "Default")
      (node (ref "U1") (pin "38") (pinfunction "PA15_38") (pintype "bidirectional"))
    )
    (net (code "70") (name "unconnected-(U1-PB2{slash}BOOT1-Pad20)") (class "Default")
      (node (ref "U1") (pin "20") (pinfunction "PB2/BOOT1_20") (pintype "bidirectional+no_connect"))
    )
    (net (code "71") (name "unconnected-(U1-PB3-Pad39)") (class "Default")
      (node (ref "U1") (pin "39") (pinfunction "PB3_39") (pintype "bidirectional"))
    )
    (net (code "72") (name "unconnected-(U1-PB4{slash}JNTRST-Pad40)") (class "Default")
      (node (ref "U1") (pin "40") (pinfunction "PB4/JNTRST_40") (pintype "bidirectional"))
    )
    (net (code "73") (name "unconnected-(U1-PB5-Pad41)") (class "Default")
      (node (ref "U1") (pin "41") (pinfunction "PB5_41") (pintype "bidirectional"))
    )
    (net (code "74") (name "unconnected-(U1-PB8-Pad45)") (class "Default")
      (node (ref "U1") (pin "45") (pinfunction "PB8_45") (pintype "bidirectional"))
    )
    (net (code "75") (name "unconnected-(U1-PB9-Pad46)") (class "Default")
      (node (ref "U1") (pin "46") (pinfunction "PB9_46") (pintype "bidirectional"))
    )
    (net (code "76") (name "unconnected-(U1-PB10-Pad21)") (class "Default")
      (node (ref "U1") (pin "21") (pinfunction "PB10_21") (pintype "bidirectional"))
    )
    (net (code "77") (name "unconnected-(U1-PB11-Pad22)") (class "Default")
      (node (ref "U1") (pin "22") (pinfunction "PB11_22") (pintype "bidirectional"))
    )
    (net (code "78") (name "unconnected-(U1-PB12-Pad25)") (class "Default")
      (node (ref "U1") (pin "25") (pinfunction "PB12_25") (pintype "bidirectional"))
    )
    (net (code "79") (name "unconnected-(U1-PB13-Pad26)") (class "Default")
      (node (ref "U1") (pin "26") (pinfunction "PB13_26") (pintype "bidirectional"))
    )
    (net (code "80") (name "unconnected-(U1-PB14-Pad27)") (class "Default")
      (node (ref "U1") (pin "27") (pinfunction "PB14_27") (pintype "bidirectional"))
    )
    (net (code "81") (name "unconnected-(U1-PC13-Pad2)") (class "Default")
      (node (ref "U1") (pin "2") (pinfunction "PC13_2") (pintype "bidirectional"))
    )
    (net (code "82") (name "unconnected-(U1-PC14-OSC32_IN-Pad3)") (class "Default")
      (node (ref "U1") (pin "3") (pinfunction "PC14-OSC32_IN_3") (pintype "bidirectional"))
    )
    (net (code "83") (name "unconnected-(U1-PC15-OSC32_OUT-Pad4)") (class "Default")
      (node (ref "U1") (pin "4") (pinfunction "PC15-OSC32_OUT_4") (pintype "bidirectional"))
    )
    (net (code "84") (name "unconnected-(U1-VBAT-Pad1)") (class "Default")
      (node (ref "U1") (pin "1") (pinfunction "VBAT_1") (pintype "power_in"))
    )
  )
)
